# USB_Hub.net
KiCad netlist of a schematic drawn in Altium Designer
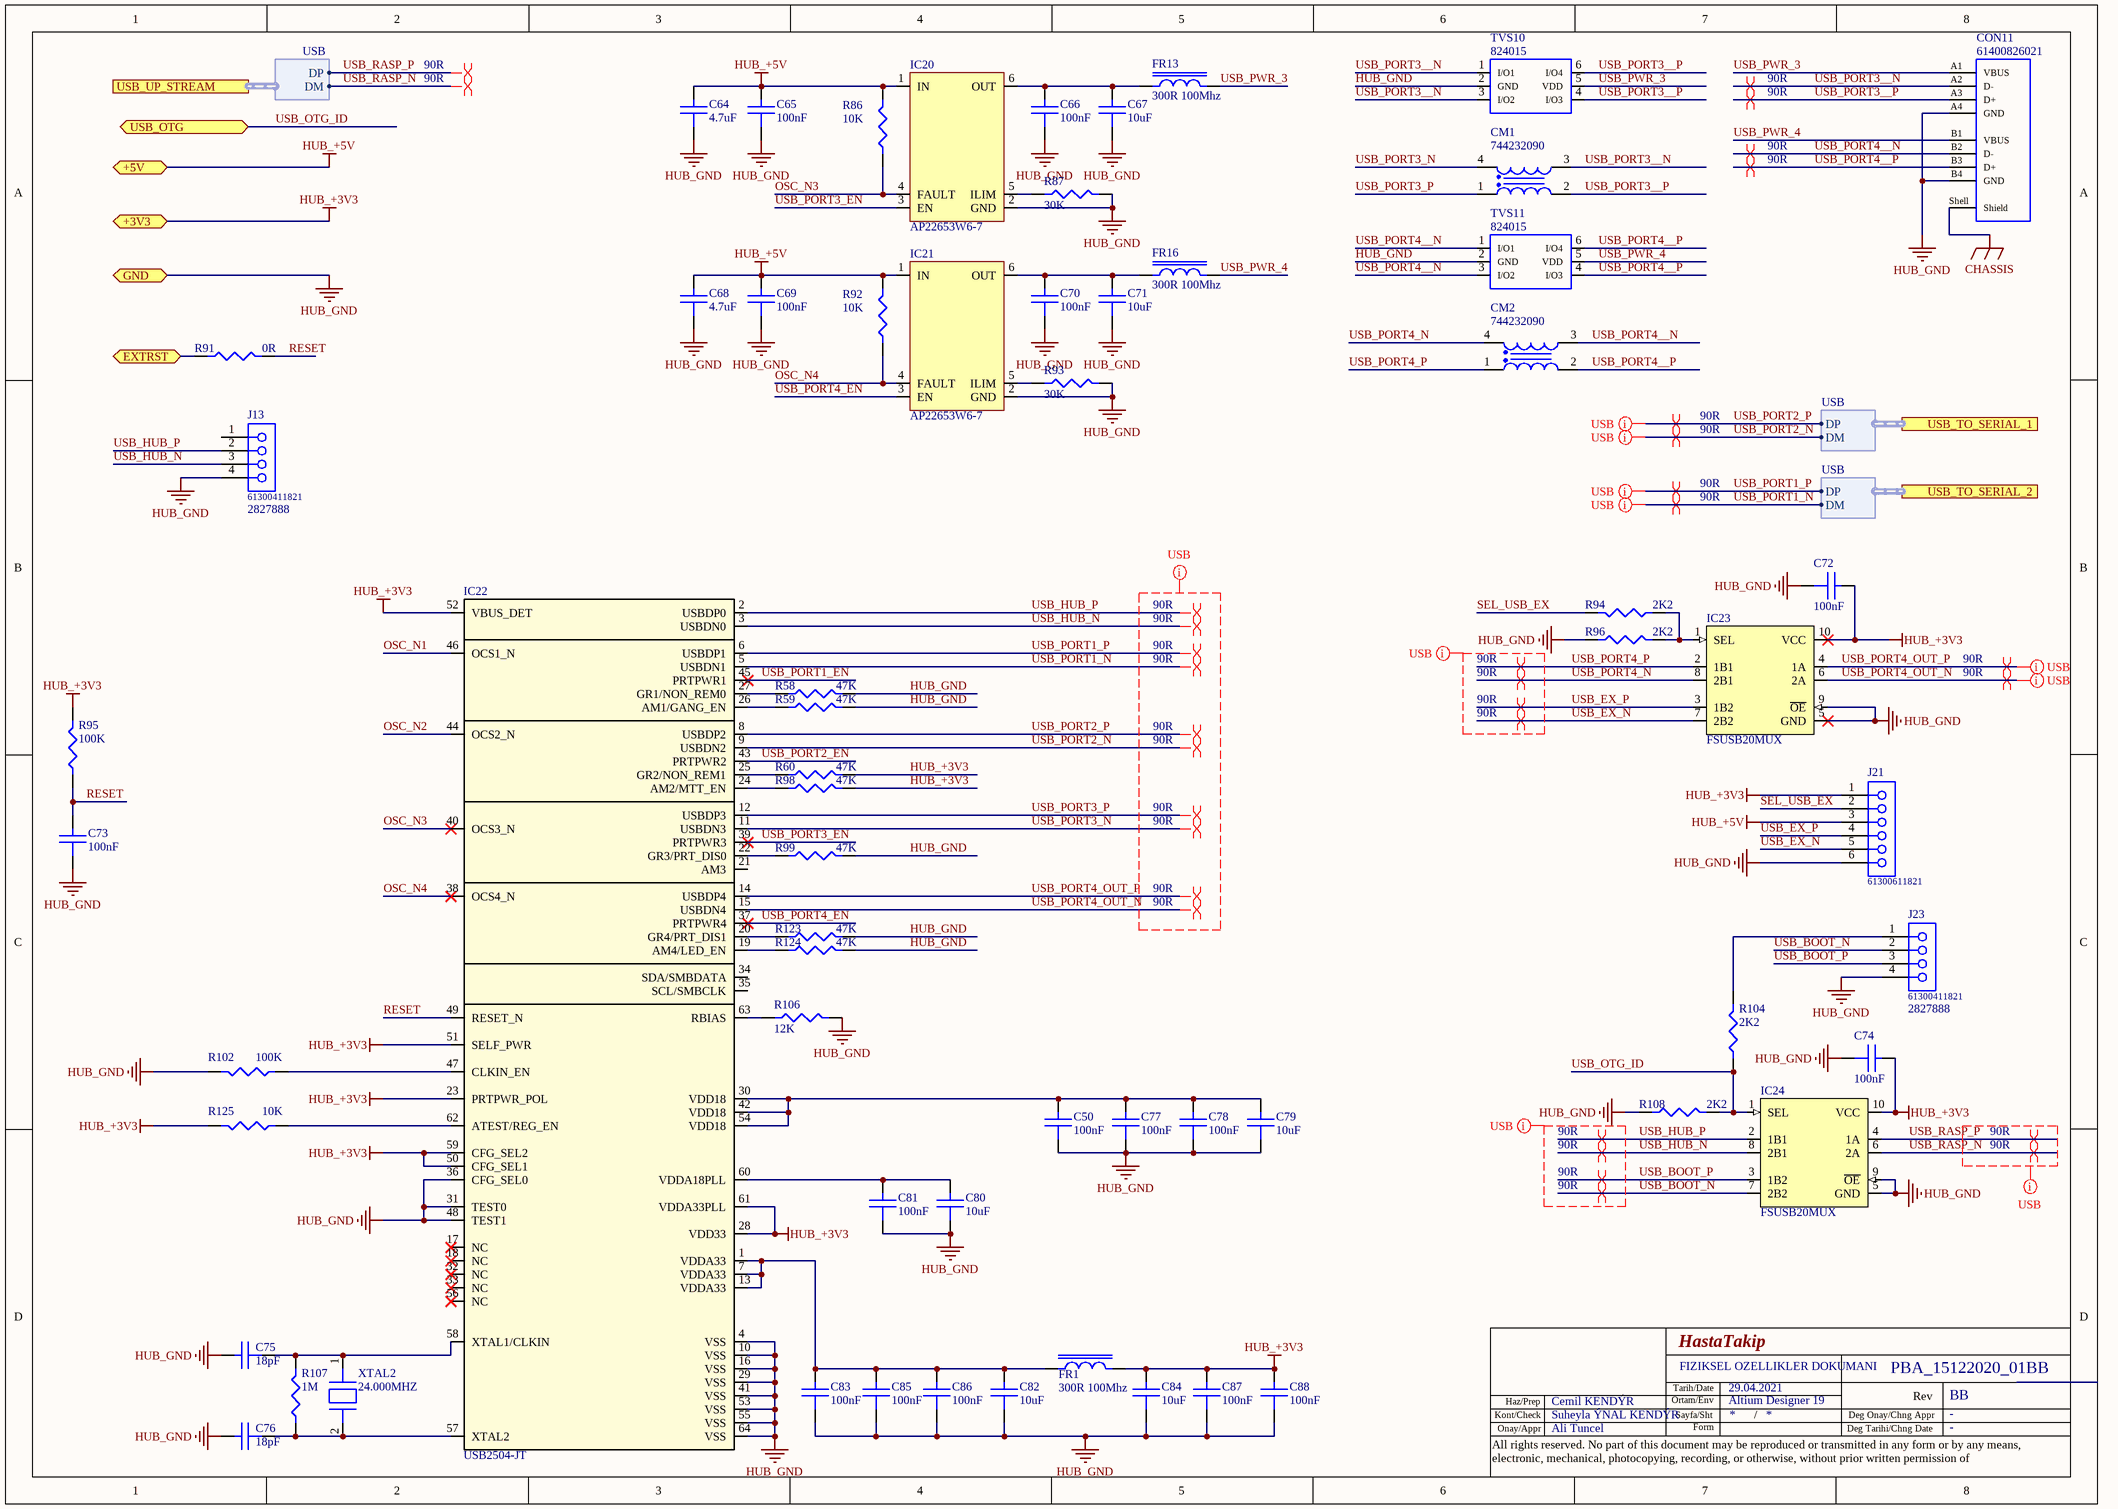
[diagram p0: USB_Hub.SchDoc]

(export (version "E")
  (design (tool "Eeschema 10.0.6"))
  (components
    (comp (ref "C50")
      (value "100nF")
      (footprint "C0603")
      (description "100nF, 25V, X7R, 10%, 0603")
      (fields
        (field (name "MANUFACTURER") "Yageo")
        (field (name "MANUFACTURER PART NUMBER") "CC0603KRX7R8BB104")
      )
      (libsource (lib "McmLibrary") (part "CC0603KRX7R8BB104"))
    )
    (comp (ref "C64")
      (value "4.7uF")
      (footprint "C0603")
      (description "4.7uF 6.3V X7R 0603")
      (fields
        (field (name "MANUFACTURER") "Yageo")
        (field (name "MANUFACTURER PART NUMBER") "CC0603MRX7R5BB475")
      )
      (libsource (lib "McmLibrary") (part "CC0603MRX7R5BB475"))
    )
    (comp (ref "C65")
      (value "100nF")
      (footprint "C0603")
      (description "100nF, 25V, X7R, 10%, 0603")
      (fields
        (field (name "MANUFACTURER") "Yageo")
        (field (name "MANUFACTURER PART NUMBER") "CC0603KRX7R8BB104")
      )
      (libsource (lib "McmLibrary") (part "CC0603KRX7R8BB104"))
    )
    (comp (ref "C66")
      (value "100nF")
      (footprint "C0603")
      (description "100nF, 25V, X7R, 10%, 0603")
      (fields
        (field (name "MANUFACTURER") "Yageo")
        (field (name "MANUFACTURER PART NUMBER") "CC0603KRX7R8BB104")
      )
      (libsource (lib "McmLibrary") (part "CC0603KRX7R8BB104"))
    )
    (comp (ref "C67")
      (value "10uF")
      (footprint "C0603")
      (description "10uF 10V X5R 20% SMD 0603 85C Paper T/R")
      (fields
        (field (name "MANUFACTURER") "Yageo")
        (field (name "MANUFACTURER PART NUMBER") "CC0603MRX5R6BB106")
      )
      (libsource (lib "McmLibrary") (part "CC0603MRX5R6BB106"))
    )
    (comp (ref "C68")
      (value "4.7uF")
      (footprint "C0603")
      (description "4.7uF 6.3V X7R 0603")
      (fields
        (field (name "MANUFACTURER") "Yageo")
        (field (name "MANUFACTURER PART NUMBER") "CC0603MRX7R5BB475")
      )
      (libsource (lib "McmLibrary") (part "CC0603MRX7R5BB475"))
    )
    (comp (ref "C69")
      (value "100nF")
      (footprint "C0603")
      (description "100nF, 25V, X7R, 10%, 0603")
      (fields
        (field (name "MANUFACTURER") "Yageo")
        (field (name "MANUFACTURER PART NUMBER") "CC0603KRX7R8BB104")
      )
      (libsource (lib "McmLibrary") (part "CC0603KRX7R8BB104"))
    )
    (comp (ref "C70")
      (value "100nF")
      (footprint "C0603")
      (description "100nF, 25V, X7R, 10%, 0603")
      (fields
        (field (name "MANUFACTURER") "Yageo")
        (field (name "MANUFACTURER PART NUMBER") "CC0603KRX7R8BB104")
      )
      (libsource (lib "McmLibrary") (part "CC0603KRX7R8BB104"))
    )
    (comp (ref "C71")
      (value "10uF")
      (footprint "C0603")
      (description "10uF 10V X5R 20% SMD 0603 85C Paper T/R")
      (fields
        (field (name "MANUFACTURER") "Yageo")
        (field (name "MANUFACTURER PART NUMBER") "CC0603MRX5R6BB106")
      )
      (libsource (lib "McmLibrary") (part "CC0603MRX5R6BB106"))
    )
    (comp (ref "C72")
      (value "100nF")
      (footprint "C0603")
      (description "100nF, 25V, X7R, 10%, 0603")
      (fields
        (field (name "MANUFACTURER") "Yageo")
        (field (name "MANUFACTURER PART NUMBER") "CC0603KRX7R8BB104")
      )
      (libsource (lib "McmLibrary") (part "CC0603KRX7R8BB104"))
    )
    (comp (ref "C73")
      (value "100nF")
      (footprint "C0603")
      (description "100nF, 25V, X7R, 10%, 0603")
      (fields
        (field (name "MANUFACTURER") "Yageo")
        (field (name "MANUFACTURER PART NUMBER") "CC0603KRX7R8BB104")
      )
      (libsource (lib "McmLibrary") (part "CC0603KRX7R8BB104"))
    )
    (comp (ref "C74")
      (value "100nF")
      (footprint "C0603")
      (description "100nF, 25V, X7R, 10%, 0603")
      (fields
        (field (name "MANUFACTURER") "Yageo")
        (field (name "MANUFACTURER PART NUMBER") "CC0603KRX7R8BB104")
      )
      (libsource (lib "McmLibrary") (part "CC0603KRX7R8BB104"))
    )
    (comp (ref "C75")
      (value "18pF")
      (footprint "C0603")
      (description "18 pF, 50 V, 0603 ± 5%, C0G / NP0")
      (fields
        (field (name "MANUFACTURER") "Yageo")
        (field (name "MANUFACTURER PART NUMBER") "CC0603JRNPO9BN180")
      )
      (libsource (lib "McmLibrary") (part "CC0603JRNPO9BN180"))
    )
    (comp (ref "C76")
      (value "18pF")
      (footprint "C0603")
      (description "18 pF, 50 V, 0603 ± 5%, C0G / NP0")
      (fields
        (field (name "MANUFACTURER") "Yageo")
        (field (name "MANUFACTURER PART NUMBER") "CC0603JRNPO9BN180")
      )
      (libsource (lib "McmLibrary") (part "CC0603JRNPO9BN180"))
    )
    (comp (ref "C77")
      (value "100nF")
      (footprint "C0603")
      (description "100nF, 25V, X7R, 10%, 0603")
      (fields
        (field (name "MANUFACTURER") "Yageo")
        (field (name "MANUFACTURER PART NUMBER") "CC0603KRX7R8BB104")
      )
      (libsource (lib "McmLibrary") (part "CC0603KRX7R8BB104"))
    )
    (comp (ref "C78")
      (value "100nF")
      (footprint "C0603")
      (description "100nF, 25V, X7R, 10%, 0603")
      (fields
        (field (name "MANUFACTURER") "Yageo")
        (field (name "MANUFACTURER PART NUMBER") "CC0603KRX7R8BB104")
      )
      (libsource (lib "McmLibrary") (part "CC0603KRX7R8BB104"))
    )
    (comp (ref "C79")
      (value "10uF")
      (footprint "C0603")
      (description "10uF 10V X5R 20% SMD 0603 85C Paper T/R")
      (fields
        (field (name "MANUFACTURER") "Yageo")
        (field (name "MANUFACTURER PART NUMBER") "CC0603MRX5R6BB106")
      )
      (libsource (lib "McmLibrary") (part "CC0603MRX5R6BB106"))
    )
    (comp (ref "C80")
      (value "10uF")
      (footprint "C0603")
      (description "10uF 10V X5R 20% SMD 0603 85C Paper T/R")
      (fields
        (field (name "MANUFACTURER") "Yageo")
        (field (name "MANUFACTURER PART NUMBER") "CC0603MRX5R6BB106")
      )
      (libsource (lib "McmLibrary") (part "CC0603MRX5R6BB106"))
    )
    (comp (ref "C81")
      (value "100nF")
      (footprint "C0603")
      (description "100nF, 25V, X7R, 10%, 0603")
      (fields
        (field (name "MANUFACTURER") "Yageo")
        (field (name "MANUFACTURER PART NUMBER") "CC0603KRX7R8BB104")
      )
      (libsource (lib "McmLibrary") (part "CC0603KRX7R8BB104"))
    )
    (comp (ref "C82")
      (value "10uF")
      (footprint "C0603")
      (description "10uF 10V X5R 20% SMD 0603 85C Paper T/R")
      (fields
        (field (name "MANUFACTURER") "Yageo")
        (field (name "MANUFACTURER PART NUMBER") "CC0603MRX5R6BB106")
      )
      (libsource (lib "McmLibrary") (part "CC0603MRX5R6BB106"))
    )
    (comp (ref "C83")
      (value "100nF")
      (footprint "C0603")
      (description "100nF, 25V, X7R, 10%, 0603")
      (fields
        (field (name "MANUFACTURER") "Yageo")
        (field (name "MANUFACTURER PART NUMBER") "CC0603KRX7R8BB104")
      )
      (libsource (lib "McmLibrary") (part "CC0603KRX7R8BB104"))
    )
    (comp (ref "C84")
      (value "10uF")
      (footprint "C0603")
      (description "10uF 10V X5R 20% SMD 0603 85C Paper T/R")
      (fields
        (field (name "MANUFACTURER") "Yageo")
        (field (name "MANUFACTURER PART NUMBER") "CC0603MRX5R6BB106")
      )
      (libsource (lib "McmLibrary") (part "CC0603MRX5R6BB106"))
    )
    (comp (ref "C85")
      (value "100nF")
      (footprint "C0603")
      (description "100nF, 25V, X7R, 10%, 0603")
      (fields
        (field (name "MANUFACTURER") "Yageo")
        (field (name "MANUFACTURER PART NUMBER") "CC0603KRX7R8BB104")
      )
      (libsource (lib "McmLibrary") (part "CC0603KRX7R8BB104"))
    )
    (comp (ref "C86")
      (value "100nF")
      (footprint "C0603")
      (description "100nF, 25V, X7R, 10%, 0603")
      (fields
        (field (name "MANUFACTURER") "Yageo")
        (field (name "MANUFACTURER PART NUMBER") "CC0603KRX7R8BB104")
      )
      (libsource (lib "McmLibrary") (part "CC0603KRX7R8BB104"))
    )
    (comp (ref "C87")
      (value "100nF")
      (footprint "C0603")
      (description "100nF, 25V, X7R, 10%, 0603")
      (fields
        (field (name "MANUFACTURER") "Yageo")
        (field (name "MANUFACTURER PART NUMBER") "CC0603KRX7R8BB104")
      )
      (libsource (lib "McmLibrary") (part "CC0603KRX7R8BB104"))
    )
    (comp (ref "C88")
      (value "100nF")
      (footprint "C0603")
      (description "100nF, 25V, X7R, 10%, 0603")
      (fields
        (field (name "MANUFACTURER") "Yageo")
        (field (name "MANUFACTURER PART NUMBER") "CC0603KRX7R8BB104")
      )
      (libsource (lib "McmLibrary") (part "CC0603KRX7R8BB104"))
    )
    (comp (ref "CM1")
      (value "744232090")
      (footprint "WE-CNSW_1206")
      (description "Common Mode Chokes Dual 90Ohm 100MHz 370mA SMD T/R")
      (fields (field (name "MANUFACTURER") "Wurth Electronics") (field (name "TOLERANCE") "25%"))
      (libsource (lib "McmLibrary") (part "744232090"))
    )
    (comp (ref "CM2")
      (value "744232090")
      (footprint "WE-CNSW_1206")
      (description "Common Mode Chokes Dual 90Ohm 100MHz 370mA SMD T/R")
      (fields (field (name "MANUFACTURER") "Wurth Electronics") (field (name "TOLERANCE") "25%"))
      (libsource (lib "McmLibrary") (part "744232090"))
    )
    (comp (ref "CON11")
      (value "61400826021")
      (footprint "61400826021")
      (description "CONN RCPT USB2.0 TYPEA STACK R/A")
      (fields (field (name "MANUFACTURER") "Wurth Electronics"))
      (libsource (lib "McmLibrary") (part "61400826021"))
    )
    (comp (ref "FR1")
      (value "300R 100Mhz")
      (footprint "WE-CBF_0603_High Current")
      (description "FERRITE BEAD 300 OHM 0603 1LN")
      (fields
        (field (name "MANUFACTURER") "Wurth Electronics")
        (field (name "MANUFACTURER PART NUMBER") "742792641")
      )
      (libsource (lib "McmLibrary") (part "742792641"))
    )
    (comp (ref "FR13")
      (value "300R 100Mhz")
      (footprint "WE-CBF_0603_High Current")
      (description "FERRITE BEAD 300 OHM 0603 1LN")
      (fields
        (field (name "MANUFACTURER") "Wurth Electronics")
        (field (name "MANUFACTURER PART NUMBER") "742792641")
      )
      (libsource (lib "McmLibrary") (part "742792641"))
    )
    (comp (ref "FR16")
      (value "300R 100Mhz")
      (footprint "WE-CBF_0603_High Current")
      (description "FERRITE BEAD 300 OHM 0603 1LN")
      (fields
        (field (name "MANUFACTURER") "Wurth Electronics")
        (field (name "MANUFACTURER PART NUMBER") "742792641")
      )
      (libsource (lib "McmLibrary") (part "742792641"))
    )
    (comp (ref "IC20")
      (value "AP22653W6-7")
      (footprint "SOT23-6")
      (description "Power Switch/Driver 1:1 P-Channel 2.1A SOT-23-6")
      (fields (field (name "MANUFACTURER") "Diodes"))
      (libsource (lib "LoadDrivers") (part "AP22653W6-7"))
    )
    (comp (ref "IC21")
      (value "AP22653W6-7")
      (footprint "SOT23-6")
      (description "Power Switch/Driver 1:1 P-Channel 2.1A SOT-23-6")
      (fields (field (name "MANUFACTURER") "Diodes"))
      (libsource (lib "LoadDrivers") (part "AP22653W6-7"))
    )
    (comp (ref "IC22")
      (value "USB2504-JT")
      (footprint "TQFP64")
      (description "Low Speed/Full Speed/High Speed Compatible 4 Port Hub USB 2.0 1.8V/3.3V 64-Pin TQFP")
      (fields (field (name "MANUFACTURER") "Microchip"))
      (libsource (lib "McmLibrary") (part "USB2504-JT"))
    )
    (comp (ref "IC23")
      (value "FSUSB20MUX")
      (footprint "MSOP-10N")
      (fields (field (name "MANUFACTURER") "ON Semiconductor / Fairchild"))
      (libsource (lib "McmLibrary") (part "FSUSB20MUX"))
    )
    (comp (ref "IC24")
      (value "FSUSB20MUX")
      (footprint "MSOP-10N")
      (fields (field (name "MANUFACTURER") "ON Semiconductor / Fairchild"))
      (libsource (lib "McmLibrary") (part "FSUSB20MUX"))
    )
    (comp (ref "J13")
      (value "61300411821")
      (footprint "61300411821")
      (description "WR-PHD Socket Header, THT, pitch 2.54mm, Single Row, Vertical, 4pin")
      (fields
        (field (name "MANUFACTURER") "Wurth Electronics")
        (field (name "SUPPLIER PART NUMBER 1") "2827888")
        (field (name "PUBLISHER") "Wurth Elektronik")
      )
      (libsource (lib "PinHeaders") (part "61300411821"))
    )
    (comp (ref "J21")
      (value "61300611821")
      (footprint "61300611821")
      (description "WR-PHD Socket Header, THT, pitch 2.54mm, Single Row, Vertical, 6pin")
      (fields (field (name "MANUFACTURER") "Wurth Elektronik") (field (name "PUBLISHER") "Wurth Elektronik"))
      (libsource (lib "PinHeaders") (part "61300611821"))
    )
    (comp (ref "J23")
      (value "61300411821")
      (footprint "61300411821")
      (description "WR-PHD Socket Header, THT, pitch 2.54mm, Single Row, Vertical, 4pin")
      (fields
        (field (name "MANUFACTURER") "Wurth Electronics")
        (field (name "SUPPLIER PART NUMBER 1") "2827888")
        (field (name "PUBLISHER") "Wurth Elektronik")
      )
      (libsource (lib "McmLibrary") (part "61300411821"))
    )
    (comp (ref "R58")
      (value "47K")
      (footprint "R0603")
      (description "47K, 50V, 1/10W, 1%, 0603")
      (fields
        (field (name "MANUFACTURER") "Yageo")
        (field (name "MANUFACTURER PART NUMBER") "RC0603FR-0747KL")
      )
      (libsource (lib "McmLibrary") (part "RC0603FR-0747KL"))
    )
    (comp (ref "R59")
      (value "47K")
      (footprint "R0603")
      (description "47K, 50V, 1/10W, 1%, 0603")
      (fields
        (field (name "MANUFACTURER") "Yageo")
        (field (name "MANUFACTURER PART NUMBER") "RC0603FR-0747KL")
      )
      (libsource (lib "McmLibrary") (part "RC0603FR-0747KL"))
    )
    (comp (ref "R60")
      (value "47K")
      (footprint "R0603")
      (description "47K, 50V, 1/10W, 1%, 0603")
      (fields
        (field (name "MANUFACTURER") "Yageo")
        (field (name "MANUFACTURER PART NUMBER") "RC0603FR-0747KL")
      )
      (libsource (lib "McmLibrary") (part "RC0603FR-0747KL"))
    )
    (comp (ref "R86")
      (value "10K")
      (footprint "R0603")
      (description "10K OHM 1% 1/10W 0603")
      (fields
        (field (name "MANUFACTURER") "Yageo")
        (field (name "MANUFACTURER PART NUMBER") "RT0603FRE0710KL")
      )
      (libsource (lib "McmLibrary") (part "RT0603FRE0710KL"))
    )
    (comp (ref "R87")
      (value "30K")
      (footprint "R0603")
      (description "30K Ohm 1% 1/10W 0603")
      (fields
        (field (name "MANUFACTURER") "Yageo")
        (field (name "MANUFACTURER PART NUMBER") "RT0603FRE0730KL")
      )
      (libsource (lib "Resistor") (part "RT0603FRE0730KL"))
    )
    (comp (ref "R91")
      (value "0R")
      (footprint "R0603")
      (description "0R, 1%, 0.1W, 0603")
      (fields
        (field (name "MANUFACTURER") "Yageo")
        (field (name "MANUFACTURER PART NUMBER") "RC0603FR-070RL")
      )
      (libsource (lib "McmLibrary") (part "RC0603FR-070RL"))
    )
    (comp (ref "R92")
      (value "10K")
      (footprint "R0603")
      (description "10K OHM 1% 1/10W 0603")
      (fields
        (field (name "MANUFACTURER") "Yageo")
        (field (name "MANUFACTURER PART NUMBER") "RT0603FRE0710KL")
      )
      (libsource (lib "McmLibrary") (part "RT0603FRE0710KL"))
    )
    (comp (ref "R93")
      (value "30K")
      (footprint "R0603")
      (description "30K Ohm 1% 1/10W 0603")
      (fields
        (field (name "MANUFACTURER") "Yageo")
        (field (name "MANUFACTURER PART NUMBER") "RT0603FRE0730KL")
      )
      (libsource (lib "Resistor") (part "RT0603FRE0730KL"))
    )
    (comp (ref "R94")
      (value "2K2")
      (footprint "R0603")
      (description "2K2, 1%, 0.1W, 0603")
      (fields
        (field (name "MANUFACTURER") "Yageo")
        (field (name "MANUFACTURER PART NUMBER") "RC0603FR-072K2L")
      )
      (libsource (lib "McmLibrary") (part "RC0603FR-072K2L"))
    )
    (comp (ref "R95")
      (value "100K")
      (footprint "R0603")
      (description "100K Ohm 1% 1/10W 0603")
      (fields
        (field (name "MANUFACTURER") "Yageo")
        (field (name "MANUFACTURER PART NUMBER") "RC0603FR-07100KL")
      )
      (libsource (lib "McmLibrary") (part "RC0603FR-07100KL"))
    )
    (comp (ref "R96")
      (value "2K2")
      (footprint "R0603")
      (description "2K2, 1%, 0.1W, 0603")
      (fields
        (field (name "MANUFACTURER") "Yageo")
        (field (name "MANUFACTURER PART NUMBER") "RC0603FR-072K2L")
      )
      (libsource (lib "McmLibrary") (part "RC0603FR-072K2L"))
    )
    (comp (ref "R98")
      (value "47K")
      (footprint "R0603")
      (description "47K, 50V, 1/10W, 1%, 0603")
      (fields
        (field (name "MANUFACTURER") "Yageo")
        (field (name "MANUFACTURER PART NUMBER") "RC0603FR-0747KL")
      )
      (libsource (lib "McmLibrary") (part "RC0603FR-0747KL"))
    )
    (comp (ref "R99")
      (value "47K")
      (footprint "R0603")
      (description "47K, 50V, 1/10W, 1%, 0603")
      (fields
        (field (name "MANUFACTURER") "Yageo")
        (field (name "MANUFACTURER PART NUMBER") "RC0603FR-0747KL")
      )
      (libsource (lib "McmLibrary") (part "RC0603FR-0747KL"))
    )
    (comp (ref "R102")
      (value "100K")
      (footprint "R0603")
      (description "100K Ohm 1% 1/10W 0603")
      (fields
        (field (name "MANUFACTURER") "Yageo")
        (field (name "MANUFACTURER PART NUMBER") "RC0603FR-07100KL")
      )
      (libsource (lib "McmLibrary") (part "RC0603FR-07100KL"))
    )
    (comp (ref "R104")
      (value "2K2")
      (footprint "R0603")
      (description "2K2, 1%, 0.1W, 0603")
      (fields
        (field (name "MANUFACTURER") "Yageo")
        (field (name "MANUFACTURER PART NUMBER") "RC0603FR-072K2L")
      )
      (libsource (lib "McmLibrary") (part "RC0603FR-072K2L"))
    )
    (comp (ref "R106")
      (value "12K")
      (footprint "R0603")
      (description "12 kohm, 0603, 75 V, 1/10 W")
      (fields
        (field (name "MANUFACTURER") "Yageo")
        (field (name "MANUFACTURER PART NUMBER") "RC0603FR-0712KL")
      )
      (libsource (lib "McmLibrary") (part "RC0603FR-0712KL"))
    )
    (comp (ref "R107")
      (value "1M")
      (footprint "R0805")
      (description "1M Ohm 0805 5% 1/8W 100ppm/C")
      (fields
        (field (name "MANUFACTURER") "Yageo")
        (field (name "MANUFACTURER PART NUMBER") "RC0805JR-071ML")
      )
      (libsource (lib "McmLibrary") (part "RC0805JR-071ML"))
    )
    (comp (ref "R108")
      (value "2K2")
      (footprint "R0603")
      (description "2K2, 1%, 0.1W, 0603")
      (fields
        (field (name "MANUFACTURER") "Yageo")
        (field (name "MANUFACTURER PART NUMBER") "RC0603FR-072K2L")
      )
      (libsource (lib "McmLibrary") (part "RC0603FR-072K2L"))
    )
    (comp (ref "R123")
      (value "47K")
      (footprint "R0603")
      (description "47K, 50V, 1/10W, 1%, 0603")
      (fields
        (field (name "MANUFACTURER") "Yageo")
        (field (name "MANUFACTURER PART NUMBER") "RC0603FR-0747KL")
      )
      (libsource (lib "McmLibrary") (part "RC0603FR-0747KL"))
    )
    (comp (ref "R124")
      (value "47K")
      (footprint "R0603")
      (description "47K, 50V, 1/10W, 1%, 0603")
      (fields
        (field (name "MANUFACTURER") "Yageo")
        (field (name "MANUFACTURER PART NUMBER") "RC0603FR-0747KL")
      )
      (libsource (lib "McmLibrary") (part "RC0603FR-0747KL"))
    )
    (comp (ref "R125")
      (value "10K")
      (footprint "R0603")
      (description "10K OHM 1% 1/10W 0603")
      (fields
        (field (name "MANUFACTURER") "Yageo")
        (field (name "MANUFACTURER PART NUMBER") "RT0603FRE0710KL")
      )
      (libsource (lib "McmLibrary") (part "RT0603FRE0710KL"))
    )
    (comp (ref "TVS10")
      (value "824015")
      (footprint "SOT-23-6")
      (description "WURTH ELEKTRONIK - 824015 - TVS Diode, 82401 Series, Bidirectional, 5 V, 13 V, SOT-23, 6 Pins")
      (fields (field (name "MANUFACTURER") "Wurth Electronics"))
      (libsource (lib "TVS") (part "824015"))
    )
    (comp (ref "TVS11")
      (value "824015")
      (footprint "SOT-23-6")
      (description "WURTH ELEKTRONIK - 824015 - TVS Diode, 82401 Series, Bidirectional, 5 V, 13 V, SOT-23, 6 Pins")
      (fields (field (name "MANUFACTURER") "Wurth Electronics"))
      (libsource (lib "TVS") (part "824015"))
    )
    (comp (ref "XTAL2")
      (value "24.000MHZ")
      (footprint "CrystalSMD")
      (description "CRYSTAL 24.0000MHZ 18PF SMD")
      (fields
        (field (name "MANUFACTURER") "Abracon")
        (field (name "MANUFACTURER PART NUMBER") "ABLS-24.000MHZ-B2-T")
      )
      (libsource (lib "McmLibrary") (part "ABLS-24.000MHZ-B2-T"))
    )
  )
  (nets
    (net (code "2") (name "/EXTRST") (class "Default")
      (node (ref "R91") (pin "1") (pinfunction "1_1") (pintype "passive"))
    )
    (net (code "3") (name "/OSC_N1") (class "Default")
      (node (ref "IC22") (pin "46") (pinfunction "OCS1_N_46") (pintype "passive"))
    )
    (net (code "4") (name "/OSC_N2") (class "Default")
      (node (ref "IC22") (pin "44") (pinfunction "OCS2_N_44") (pintype "passive"))
    )
    (net (code "5") (name "/OSC_N3") (class "Default")
      (node (ref "IC20") (pin "4") (pinfunction "FAULT_4") (pintype "passive"))
      (node (ref "IC22") (pin "40") (pinfunction "OCS3_N_40") (pintype "passive"))
      (node (ref "R86") (pin "1") (pinfunction "1_1") (pintype "passive"))
    )
    (net (code "6") (name "/OSC_N4") (class "Default")
      (node (ref "IC21") (pin "4") (pinfunction "FAULT_4") (pintype "passive"))
      (node (ref "IC22") (pin "38") (pinfunction "OCS4_N_38") (pintype "passive"))
      (node (ref "R92") (pin "1") (pinfunction "1_1") (pintype "passive"))
    )
    (net (code "7") (name "/RESET") (class "Default")
      (node (ref "C73") (pin "1") (pintype "passive"))
      (node (ref "IC22") (pin "49") (pinfunction "RESET_N_49") (pintype "passive"))
      (node (ref "R91") (pin "2") (pinfunction "2_2") (pintype "passive"))
      (node (ref "R95") (pin "1") (pinfunction "1_1") (pintype "passive"))
    )
    (net (code "8") (name "/SEL_USB_EX") (class "Default")
      (node (ref "J21") (pin "2") (pinfunction "2_2") (pintype "passive"))
      (node (ref "R94") (pin "2") (pinfunction "2_2") (pintype "passive"))
    )
    (net (code "9") (name "/USB_BOOT_N") (class "Default")
      (node (ref "IC24") (pin "7") (pinfunction "2B2_7") (pintype "bidirectional"))
      (node (ref "J23") (pin "2") (pinfunction "2_2") (pintype "passive"))
    )
    (net (code "10") (name "/USB_BOOT_P") (class "Default")
      (node (ref "IC24") (pin "3") (pinfunction "1B2_3") (pintype "bidirectional"))
      (node (ref "J23") (pin "3") (pinfunction "3_3") (pintype "passive"))
    )
    (net (code "11") (name "/USB_EX_N") (class "Default")
      (node (ref "IC23") (pin "7") (pinfunction "2B2_7") (pintype "bidirectional"))
      (node (ref "J21") (pin "5") (pinfunction "5_5") (pintype "passive"))
    )
    (net (code "12") (name "/USB_EX_P") (class "Default")
      (node (ref "IC23") (pin "3") (pinfunction "1B2_3") (pintype "bidirectional"))
      (node (ref "J21") (pin "4") (pinfunction "4_4") (pintype "passive"))
    )
    (net (code "13") (name "/USB_HUB_N") (class "Default")
      (node (ref "IC22") (pin "3") (pinfunction "USBDN0_3") (pintype "passive"))
      (node (ref "IC24") (pin "8") (pinfunction "2B1_8") (pintype "bidirectional"))
      (node (ref "J13") (pin "3") (pinfunction "3_3") (pintype "passive"))
    )
    (net (code "14") (name "/USB_HUB_P") (class "Default")
      (node (ref "IC22") (pin "2") (pinfunction "USBDP0_2") (pintype "passive"))
      (node (ref "IC24") (pin "2") (pinfunction "1B1_2") (pintype "bidirectional"))
      (node (ref "J13") (pin "2") (pinfunction "2_2") (pintype "passive"))
    )
    (net (code "15") (name "/USB_OTG_ID") (class "Default")
      (node (ref "IC24") (pin "1") (pinfunction "SEL_1") (pintype "input"))
      (node (ref "R104") (pin "1") (pinfunction "1_1") (pintype "passive"))
      (node (ref "R108") (pin "2") (pinfunction "2_2") (pintype "passive"))
    )
    (net (code "16") (name "/USB_PORT1_EN") (class "Default")
      (node (ref "IC22") (pin "45") (pinfunction "PRTPWR1_45") (pintype "passive+no_connect"))
    )
    (net (code "17") (name "/USB_PORT1_N") (class "Default")
      (node (ref "IC22") (pin "5") (pinfunction "USBDN1_5") (pintype "passive"))
    )
    (net (code "18") (name "/USB_PORT1_P") (class "Default")
      (node (ref "IC22") (pin "6") (pinfunction "USBDP1_6") (pintype "passive"))
    )
    (net (code "19") (name "/USB_PORT2_EN") (class "Default")
      (node (ref "IC22") (pin "43") (pinfunction "PRTPWR2_43") (pintype "passive"))
    )
    (net (code "20") (name "/USB_PORT2_N") (class "Default")
      (node (ref "IC22") (pin "9") (pinfunction "USBDN2_9") (pintype "passive"))
    )
    (net (code "21") (name "/USB_PORT2_P") (class "Default")
      (node (ref "IC22") (pin "8") (pinfunction "USBDP2_8") (pintype "passive"))
    )
    (net (code "22") (name "/USB_PORT3_EN") (class "Default")
      (node (ref "IC20") (pin "3") (pinfunction "EN_3") (pintype "passive"))
      (node (ref "IC22") (pin "39") (pinfunction "PRTPWR3_39") (pintype "passive"))
    )
    (net (code "23") (name "/USB_PORT3_N") (class "Default")
      (node (ref "CM1") (pin "4") (pinfunction "4_4") (pintype "passive"))
      (node (ref "IC22") (pin "11") (pinfunction "USBDN3_11") (pintype "passive"))
    )
    (net (code "24") (name "/USB_PORT3_P") (class "Default")
      (node (ref "CM1") (pin "1") (pinfunction "1_1") (pintype "passive"))
      (node (ref "IC22") (pin "12") (pinfunction "USBDP3_12") (pintype "passive"))
    )
    (net (code "25") (name "/USB_PORT3__N") (class "Default")
      (node (ref "CM1") (pin "3") (pinfunction "3_3") (pintype "passive"))
      (node (ref "CON11") (pin "A2") (pinfunction "D-_A2") (pintype "passive"))
      (node (ref "TVS10") (pin "1") (pinfunction "I/O1_1") (pintype "passive"))
      (node (ref "TVS10") (pin "3") (pinfunction "I/O2_3") (pintype "passive"))
    )
    (net (code "26") (name "/USB_PORT3__P") (class "Default")
      (node (ref "CM1") (pin "2") (pinfunction "2_2") (pintype "passive"))
      (node (ref "CON11") (pin "A3") (pinfunction "D+_A3") (pintype "passive"))
      (node (ref "TVS10") (pin "4") (pinfunction "I/O3_4") (pintype "passive"))
      (node (ref "TVS10") (pin "6") (pinfunction "I/O4_6") (pintype "passive"))
    )
    (net (code "27") (name "/USB_PORT4_EN") (class "Default")
      (node (ref "IC21") (pin "3") (pinfunction "EN_3") (pintype "passive"))
      (node (ref "IC22") (pin "37") (pinfunction "PRTPWR4_37") (pintype "passive"))
    )
    (net (code "28") (name "/USB_PORT4_N") (class "Default")
      (node (ref "CM2") (pin "4") (pinfunction "4_4") (pintype "passive"))
      (node (ref "IC23") (pin "8") (pinfunction "2B1_8") (pintype "bidirectional"))
    )
    (net (code "29") (name "/USB_PORT4_OUT_N") (class "Default")
      (node (ref "IC22") (pin "15") (pinfunction "USBDN4_15") (pintype "passive"))
      (node (ref "IC23") (pin "6") (pinfunction "2A_6") (pintype "bidirectional"))
    )
    (net (code "30") (name "/USB_PORT4_OUT_P") (class "Default")
      (node (ref "IC22") (pin "14") (pinfunction "USBDP4_14") (pintype "passive"))
      (node (ref "IC23") (pin "4") (pinfunction "1A_4") (pintype "bidirectional"))
    )
    (net (code "31") (name "/USB_PORT4_P") (class "Default")
      (node (ref "CM2") (pin "1") (pinfunction "1_1") (pintype "passive"))
      (node (ref "IC23") (pin "2") (pinfunction "1B1_2") (pintype "bidirectional"))
    )
    (net (code "32") (name "/USB_PORT4__N") (class "Default")
      (node (ref "CM2") (pin "3") (pinfunction "3_3") (pintype "passive"))
      (node (ref "CON11") (pin "B2") (pinfunction "D-_B2") (pintype "passive"))
      (node (ref "TVS11") (pin "1") (pinfunction "I/O1_1") (pintype "passive"))
      (node (ref "TVS11") (pin "3") (pinfunction "I/O2_3") (pintype "passive"))
    )
    (net (code "33") (name "/USB_PORT4__P") (class "Default")
      (node (ref "CM2") (pin "2") (pinfunction "2_2") (pintype "passive"))
      (node (ref "CON11") (pin "B3") (pinfunction "D+_B3") (pintype "passive"))
      (node (ref "TVS11") (pin "4") (pinfunction "I/O3_4") (pintype "passive"))
      (node (ref "TVS11") (pin "6") (pinfunction "I/O4_6") (pintype "passive"))
    )
    (net (code "34") (name "/USB_PWR_3") (class "Default")
      (node (ref "CON11") (pin "A1") (pinfunction "VBUS_A1") (pintype "passive"))
      (node (ref "FR13") (pin "2") (pinfunction "2_2") (pintype "passive"))
      (node (ref "TVS10") (pin "5") (pinfunction "VDD_5") (pintype "passive"))
    )
    (net (code "35") (name "/USB_PWR_4") (class "Default")
      (node (ref "CON11") (pin "B1") (pinfunction "VBUS_B1") (pintype "passive"))
      (node (ref "FR16") (pin "2") (pinfunction "2_2") (pintype "passive"))
      (node (ref "TVS11") (pin "5") (pinfunction "VDD_5") (pintype "passive"))
    )
    (net (code "36") (name "/USB_RASP_N") (class "Default")
      (node (ref "IC24") (pin "6") (pinfunction "2A_6") (pintype "bidirectional"))
    )
    (net (code "37") (name "/USB_RASP_P") (class "Default")
      (node (ref "IC24") (pin "4") (pinfunction "1A_4") (pintype "bidirectional"))
    )
    (net (code "39") (name "CHASSIS") (class "Default")
      (node (ref "CON11") (pin "Shell") (pinfunction "Shield_Shell") (pintype "passive"))
    )
    (net (code "40") (name "HUB_+3V3") (class "Default")
      (node (ref "C72") (pin "1") (pintype "passive"))
      (node (ref "C74") (pin "1") (pintype "passive"))
      (node (ref "C84") (pin "1") (pintype "passive"))
      (node (ref "C87") (pin "1") (pintype "passive"))
      (node (ref "C88") (pin "1") (pintype "passive"))
      (node (ref "FR1") (pin "2") (pinfunction "2_2") (pintype "passive"))
      (node (ref "IC22") (pin "23") (pinfunction "PRTPWR_POL_23") (pintype "passive"))
      (node (ref "IC22") (pin "28") (pinfunction "VDD33_28") (pintype "passive"))
      (node (ref "IC22") (pin "50") (pinfunction "CFG_SEL1_50") (pintype "passive"))
      (node (ref "IC22") (pin "51") (pinfunction "SELF_PWR_51") (pintype "passive"))
      (node (ref "IC22") (pin "52") (pinfunction "VBUS_DET_52") (pintype "passive"))
      (node (ref "IC22") (pin "59") (pinfunction "CFG_SEL2_59") (pintype "passive"))
      (node (ref "IC22") (pin "61") (pinfunction "VDDA33PLL_61") (pintype "passive"))
      (node (ref "IC23") (pin "10") (pinfunction "VCC_10") (pintype "power_in"))
      (node (ref "IC24") (pin "10") (pinfunction "VCC_10") (pintype "power_in"))
      (node (ref "J21") (pin "1") (pinfunction "1_1") (pintype "passive"))
      (node (ref "R125") (pin "2") (pinfunction "2_2") (pintype "passive"))
      (node (ref "R60") (pin "2") (pinfunction "2_2") (pintype "passive"))
      (node (ref "R95") (pin "2") (pinfunction "2_2") (pintype "passive"))
      (node (ref "R98") (pin "2") (pinfunction "2_2") (pintype "passive"))
    )
    (net (code "41") (name "HUB_+5V") (class "Default")
      (node (ref "C64") (pin "1") (pintype "passive"))
      (node (ref "C65") (pin "1") (pintype "passive"))
      (node (ref "C68") (pin "1") (pintype "passive"))
      (node (ref "C69") (pin "1") (pintype "passive"))
      (node (ref "IC20") (pin "1") (pinfunction "IN_1") (pintype "passive"))
      (node (ref "IC21") (pin "1") (pinfunction "IN_1") (pintype "passive"))
      (node (ref "J21") (pin "3") (pinfunction "3_3") (pintype "passive"))
      (node (ref "R86") (pin "2") (pinfunction "2_2") (pintype "passive"))
      (node (ref "R92") (pin "2") (pinfunction "2_2") (pintype "passive"))
    )
    (net (code "42") (name "HUB_GND") (class "Default")
      (node (ref "C50") (pin "2") (pintype "passive"))
      (node (ref "C64") (pin "2") (pintype "passive"))
      (node (ref "C65") (pin "2") (pintype "passive"))
      (node (ref "C66") (pin "2") (pintype "passive"))
      (node (ref "C67") (pin "2") (pintype "passive"))
      (node (ref "C68") (pin "2") (pintype "passive"))
      (node (ref "C69") (pin "2") (pintype "passive"))
      (node (ref "C70") (pin "2") (pintype "passive"))
      (node (ref "C71") (pin "2") (pintype "passive"))
      (node (ref "C72") (pin "2") (pintype "passive"))
      (node (ref "C73") (pin "2") (pintype "passive"))
      (node (ref "C74") (pin "2") (pintype "passive"))
      (node (ref "C75") (pin "1") (pintype "passive"))
      (node (ref "C76") (pin "1") (pintype "passive"))
      (node (ref "C77") (pin "2") (pintype "passive"))
      (node (ref "C78") (pin "2") (pintype "passive"))
      (node (ref "C79") (pin "2") (pintype "passive"))
      (node (ref "C80") (pin "2") (pintype "passive"))
      (node (ref "C81") (pin "2") (pintype "passive"))
      (node (ref "C82") (pin "2") (pintype "passive"))
      (node (ref "C83") (pin "2") (pintype "passive"))
      (node (ref "C84") (pin "2") (pintype "passive"))
      (node (ref "C85") (pin "2") (pintype "passive"))
      (node (ref "C86") (pin "2") (pintype "passive"))
      (node (ref "C87") (pin "2") (pintype "passive"))
      (node (ref "C88") (pin "2") (pintype "passive"))
      (node (ref "CON11") (pin "A4") (pinfunction "GND_A4") (pintype "passive"))
      (node (ref "CON11") (pin "B4") (pinfunction "GND_B4") (pintype "passive"))
      (node (ref "IC20") (pin "2") (pinfunction "GND_2") (pintype "passive"))
      (node (ref "IC21") (pin "2") (pinfunction "GND_2") (pintype "passive"))
      (node (ref "IC22") (pin "10") (pinfunction "VSS_10") (pintype "passive"))
      (node (ref "IC22") (pin "16") (pinfunction "VSS_16") (pintype "passive"))
      (node (ref "IC22") (pin "29") (pinfunction "VSS_29") (pintype "passive"))
      (node (ref "IC22") (pin "31") (pinfunction "TEST0_31") (pintype "passive"))
      (node (ref "IC22") (pin "36") (pinfunction "CFG_SEL0_36") (pintype "passive"))
      (node (ref "IC22") (pin "4") (pinfunction "VSS_4") (pintype "passive"))
      (node (ref "IC22") (pin "41") (pinfunction "VSS_41") (pintype "passive"))
      (node (ref "IC22") (pin "48") (pinfunction "TEST1_48") (pintype "passive"))
      (node (ref "IC22") (pin "53") (pinfunction "VSS_53") (pintype "passive"))
      (node (ref "IC22") (pin "55") (pinfunction "VSS_55") (pintype "passive"))
      (node (ref "IC22") (pin "64") (pinfunction "VSS_64") (pintype "passive"))
      (node (ref "IC23") (pin "5") (pinfunction "GND_5") (pintype "power_in"))
      (node (ref "IC23") (pin "9") (pinfunction "~{OE}_9") (pintype "input"))
      (node (ref "IC24") (pin "5") (pinfunction "GND_5") (pintype "power_in"))
      (node (ref "IC24") (pin "9") (pinfunction "~{OE}_9") (pintype "input"))
      (node (ref "J13") (pin "4") (pinfunction "4_4") (pintype "passive"))
      (node (ref "J21") (pin "6") (pinfunction "6_6") (pintype "passive"))
      (node (ref "J23") (pin "4") (pinfunction "4_4") (pintype "passive"))
      (node (ref "R102") (pin "2") (pinfunction "2_2") (pintype "passive"))
      (node (ref "R106") (pin "2") (pinfunction "2_2") (pintype "passive"))
      (node (ref "R108") (pin "1") (pinfunction "1_1") (pintype "passive"))
      (node (ref "R123") (pin "2") (pinfunction "2_2") (pintype "passive"))
      (node (ref "R124") (pin "2") (pinfunction "2_2") (pintype "passive"))
      (node (ref "R58") (pin "2") (pinfunction "2_2") (pintype "passive"))
      (node (ref "R59") (pin "2") (pinfunction "2_2") (pintype "passive"))
      (node (ref "R87") (pin "2") (pinfunction "2_2") (pintype "passive"))
      (node (ref "R93") (pin "2") (pinfunction "2_2") (pintype "passive"))
      (node (ref "R96") (pin "1") (pinfunction "1_1") (pintype "passive"))
      (node (ref "R99") (pin "2") (pinfunction "2_2") (pintype "passive"))
      (node (ref "TVS10") (pin "2") (pinfunction "GND_2") (pintype "passive"))
      (node (ref "TVS11") (pin "2") (pinfunction "GND_2") (pintype "passive"))
    )
    (net (code "43") (name "Net-(C50-Pad1)") (class "Default")
      (node (ref "C50") (pin "1") (pintype "passive"))
      (node (ref "C77") (pin "1") (pintype "passive"))
      (node (ref "C78") (pin "1") (pintype "passive"))
      (node (ref "C79") (pin "1") (pintype "passive"))
      (node (ref "IC22") (pin "30") (pinfunction "VDD18_30") (pintype "passive"))
      (node (ref "IC22") (pin "42") (pinfunction "VDD18_42") (pintype "passive"))
      (node (ref "IC22") (pin "54") (pinfunction "VDD18_54") (pintype "passive"))
    )
    (net (code "44") (name "Net-(C82-Pad1)") (class "Default")
      (node (ref "C82") (pin "1") (pintype "passive"))
      (node (ref "C83") (pin "1") (pintype "passive"))
      (node (ref "C85") (pin "1") (pintype "passive"))
      (node (ref "C86") (pin "1") (pintype "passive"))
      (node (ref "FR1") (pin "1") (pinfunction "1_1") (pintype "passive"))
      (node (ref "IC22") (pin "1") (pinfunction "VDDA33_1") (pintype "passive"))
      (node (ref "IC22") (pin "13") (pinfunction "VDDA33_13") (pintype "passive"))
      (node (ref "IC22") (pin "7") (pinfunction "VDDA33_7") (pintype "passive"))
    )
    (net (code "45") (name "Net-(IC20-ILIM)") (class "Default")
      (node (ref "IC20") (pin "5") (pinfunction "ILIM_5") (pintype "passive"))
      (node (ref "R87") (pin "1") (pinfunction "1_1") (pintype "passive"))
    )
    (net (code "46") (name "Net-(IC20-OUT)") (class "Default")
      (node (ref "C66") (pin "1") (pintype "passive"))
      (node (ref "C67") (pin "1") (pintype "passive"))
      (node (ref "FR13") (pin "1") (pinfunction "1_1") (pintype "passive"))
      (node (ref "IC20") (pin "6") (pinfunction "OUT_6") (pintype "passive"))
    )
    (net (code "47") (name "Net-(IC21-ILIM)") (class "Default")
      (node (ref "IC21") (pin "5") (pinfunction "ILIM_5") (pintype "passive"))
      (node (ref "R93") (pin "1") (pinfunction "1_1") (pintype "passive"))
    )
    (net (code "48") (name "Net-(IC21-OUT)") (class "Default")
      (node (ref "C70") (pin "1") (pintype "passive"))
      (node (ref "C71") (pin "1") (pintype "passive"))
      (node (ref "FR16") (pin "1") (pinfunction "1_1") (pintype "passive"))
      (node (ref "IC21") (pin "6") (pinfunction "OUT_6") (pintype "passive"))
    )
    (net (code "49") (name "Net-(IC22-AM1{slash}GANG_EN)") (class "Default")
      (node (ref "IC22") (pin "26") (pinfunction "AM1/GANG_EN_26") (pintype "passive"))
      (node (ref "R59") (pin "1") (pinfunction "1_1") (pintype "passive"))
    )
    (net (code "50") (name "Net-(IC22-AM2{slash}MTT_EN)") (class "Default")
      (node (ref "IC22") (pin "24") (pinfunction "AM2/MTT_EN_24") (pintype "passive"))
      (node (ref "R98") (pin "1") (pinfunction "1_1") (pintype "passive"))
    )
    (net (code "51") (name "Net-(IC22-AM4{slash}LED_EN)") (class "Default")
      (node (ref "IC22") (pin "19") (pinfunction "AM4/LED_EN_19") (pintype "passive"))
      (node (ref "R124") (pin "1") (pinfunction "1_1") (pintype "passive"))
    )
    (net (code "52") (name "Net-(IC22-ATEST{slash}REG_EN)") (class "Default")
      (node (ref "IC22") (pin "62") (pinfunction "ATEST/REG_EN_62") (pintype "passive"))
      (node (ref "R125") (pin "1") (pinfunction "1_1") (pintype "passive"))
    )
    (net (code "53") (name "Net-(IC22-CLKIN_EN)") (class "Default")
      (node (ref "IC22") (pin "47") (pinfunction "CLKIN_EN_47") (pintype "passive"))
      (node (ref "R102") (pin "1") (pinfunction "1_1") (pintype "passive"))
    )
    (net (code "54") (name "Net-(IC22-GR1{slash}NON_REM0)") (class "Default")
      (node (ref "IC22") (pin "27") (pinfunction "GR1/NON_REM0_27") (pintype "passive"))
      (node (ref "R58") (pin "1") (pinfunction "1_1") (pintype "passive"))
    )
    (net (code "55") (name "Net-(IC22-GR2{slash}NON_REM1)") (class "Default")
      (node (ref "IC22") (pin "25") (pinfunction "GR2/NON_REM1_25") (pintype "passive"))
      (node (ref "R60") (pin "1") (pinfunction "1_1") (pintype "passive"))
    )
    (net (code "56") (name "Net-(IC22-GR3{slash}PRT_DIS0)") (class "Default")
      (node (ref "IC22") (pin "22") (pinfunction "GR3/PRT_DIS0_22") (pintype "passive"))
      (node (ref "R99") (pin "1") (pinfunction "1_1") (pintype "passive"))
    )
    (net (code "57") (name "Net-(IC22-GR4{slash}PRT_DIS1)") (class "Default")
      (node (ref "IC22") (pin "20") (pinfunction "GR4/PRT_DIS1_20") (pintype "passive"))
      (node (ref "R123") (pin "1") (pinfunction "1_1") (pintype "passive"))
    )
    (net (code "58") (name "Net-(IC22-RBIAS)") (class "Default")
      (node (ref "IC22") (pin "63") (pinfunction "RBIAS_63") (pintype "passive"))
      (node (ref "R106") (pin "1") (pinfunction "1_1") (pintype "passive"))
    )
    (net (code "59") (name "Net-(IC22-VDDA18PLL)") (class "Default")
      (node (ref "C80") (pin "1") (pintype "passive"))
      (node (ref "C81") (pin "1") (pintype "passive"))
      (node (ref "IC22") (pin "60") (pinfunction "VDDA18PLL_60") (pintype "passive"))
    )
    (net (code "60") (name "Net-(IC22-XTAL1{slash}CLKIN)") (class "Default")
      (node (ref "C75") (pin "2") (pintype "passive"))
      (node (ref "IC22") (pin "58") (pinfunction "XTAL1/CLKIN_58") (pintype "passive"))
      (node (ref "R107") (pin "2") (pinfunction "2_2") (pintype "passive"))
      (node (ref "XTAL2") (pin "1") (pinfunction "1_1") (pintype "passive"))
    )
    (net (code "61") (name "Net-(IC22-XTAL2)") (class "Default")
      (node (ref "C76") (pin "2") (pintype "passive"))
      (node (ref "IC22") (pin "57") (pinfunction "XTAL2_57") (pintype "passive"))
      (node (ref "R107") (pin "1") (pinfunction "1_1") (pintype "passive"))
      (node (ref "XTAL2") (pin "2") (pinfunction "2_2") (pintype "passive"))
    )
    (net (code "62") (name "Net-(IC23-SEL)") (class "Default")
      (node (ref "IC23") (pin "1") (pinfunction "SEL_1") (pintype "input"))
      (node (ref "R94") (pin "1") (pinfunction "1_1") (pintype "passive"))
      (node (ref "R96") (pin "2") (pinfunction "2_2") (pintype "passive"))
    )
    (net (code "63") (name "Net-(J23-Pad1)") (class "Default")
      (node (ref "J23") (pin "1") (pinfunction "1_1") (pintype "passive"))
      (node (ref "R104") (pin "2") (pinfunction "2_2") (pintype "passive"))
    )
    (net (code "64") (name "unconnected-(IC22-AM3-Pad21)") (class "Default")
      (node (ref "IC22") (pin "21") (pinfunction "AM3_21") (pintype "passive"))
    )
    (net (code "65") (name "unconnected-(IC22-NC-Pad17)") (class "Default")
      (node (ref "IC22") (pin "17") (pinfunction "NC_17") (pintype "passive+no_connect"))
    )
    (net (code "66") (name "unconnected-(IC22-NC-Pad18)") (class "Default")
      (node (ref "IC22") (pin "18") (pinfunction "NC_18") (pintype "passive+no_connect"))
    )
    (net (code "67") (name "unconnected-(IC22-NC-Pad32)") (class "Default")
      (node (ref "IC22") (pin "32") (pinfunction "NC_32") (pintype "passive+no_connect"))
    )
    (net (code "68") (name "unconnected-(IC22-NC-Pad33)") (class "Default")
      (node (ref "IC22") (pin "33") (pinfunction "NC_33") (pintype "passive+no_connect"))
    )
    (net (code "69") (name "unconnected-(IC22-NC-Pad56)") (class "Default")
      (node (ref "IC22") (pin "56") (pinfunction "NC_56") (pintype "passive+no_connect"))
    )
    (net (code "70") (name "unconnected-(IC22-SCL{slash}SMBCLK-Pad35)") (class "Default")
      (node (ref "IC22") (pin "35") (pinfunction "SCL/SMBCLK_35") (pintype "passive"))
    )
    (net (code "71") (name "unconnected-(IC22-SDA{slash}SMBDATA-Pad34)") (class "Default")
      (node (ref "IC22") (pin "34") (pinfunction "SDA/SMBDATA_34") (pintype "passive"))
    )
    (net (code "72") (name "unconnected-(J13-Pad1)") (class "Default")
      (node (ref "J13") (pin "1") (pinfunction "1_1") (pintype "passive"))
    )
  )
)
